# espbot.net
KiCad netlist of a schematic drawn in EAGLE
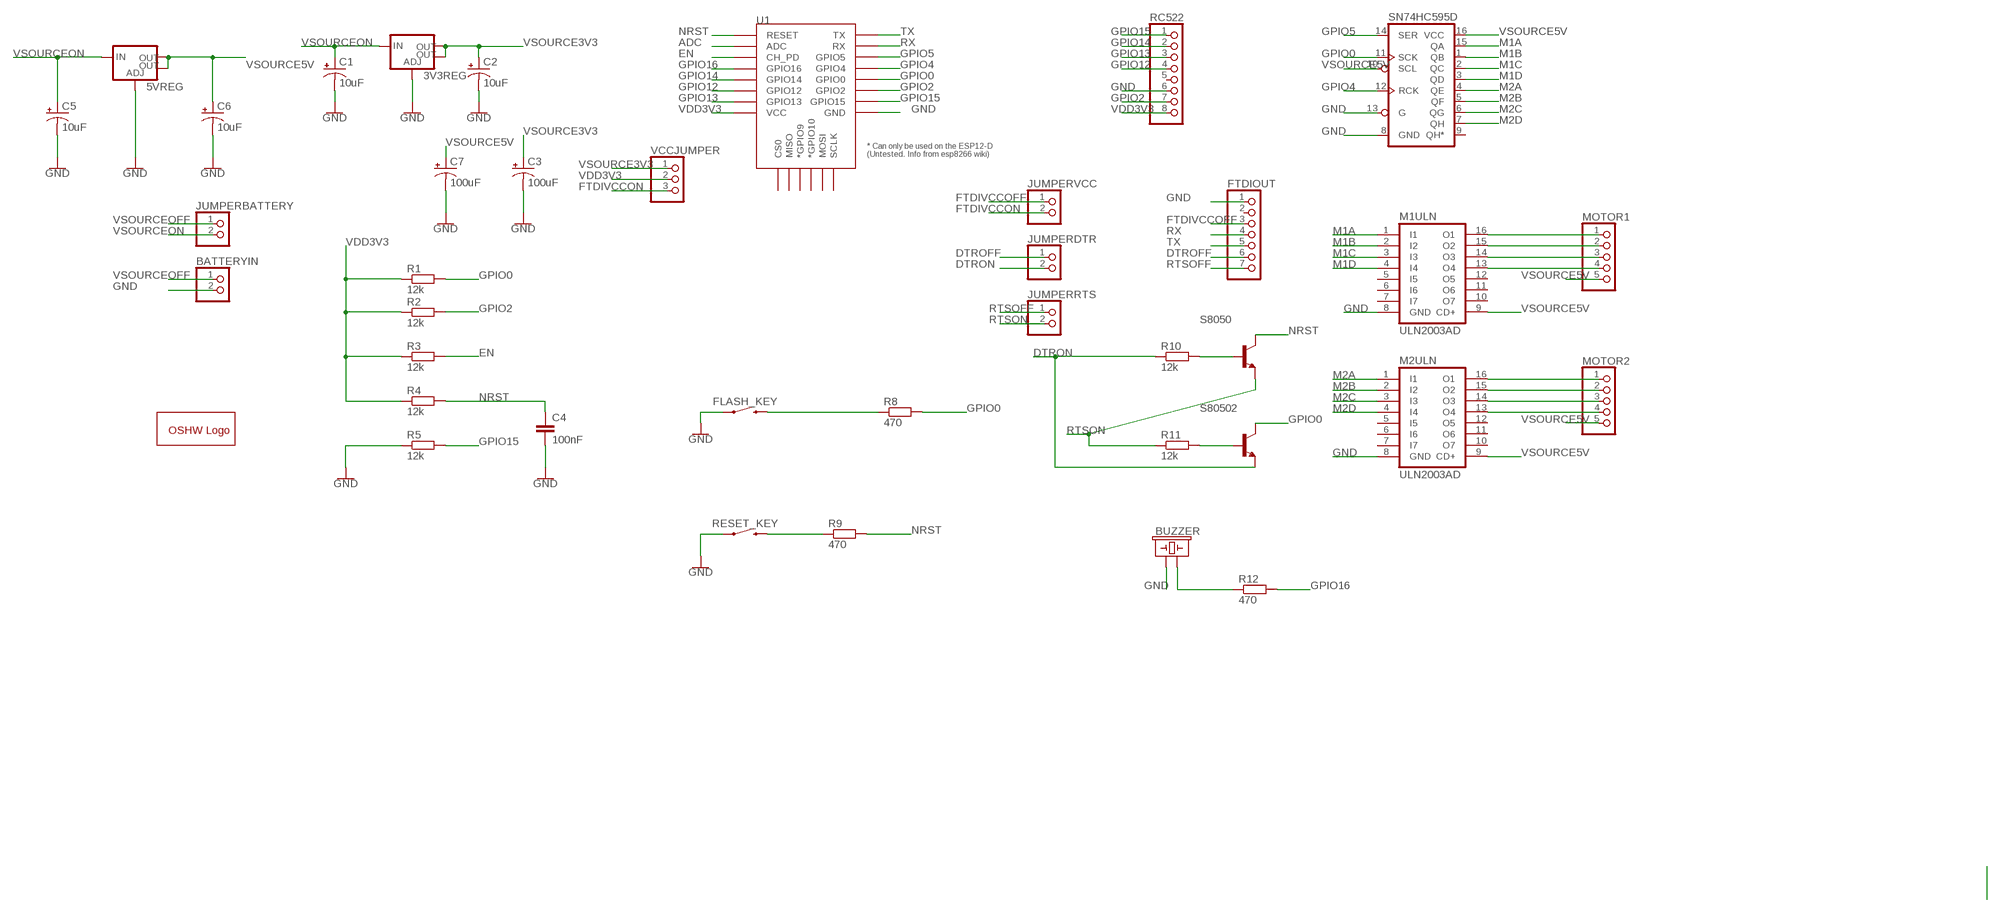
[diagram p0: schematic, sheet 1]

(export (version "E")
  (design (tool "Eeschema 10.0.6"))
  (components
    (comp (ref "3V3REG")
      (value "V_REG_LM1117SOT223")
      (footprint "eagle-import:SOT223")
      (libsource (lib "eagle-import") (part "V_REG_LM1117SOT223"))
    )
    (comp (ref "5VREG")
      (value "V_REG_LM1117SOT223")
      (footprint "eagle-import:SOT223")
      (libsource (lib "eagle-import") (part "V_REG_LM1117SOT223"))
    )
    (comp (ref "BATTERYIN")
      (value "PINHD-1X2")
      (footprint "eagle-import:1X02")
      (libsource (lib "eagle-import") (part "PINHD-1X2"))
    )
    (comp (ref "BUZZER")
      (value "BUZZER-PTH")
      (footprint "eagle-import:BUZZER-12MM")
      (libsource (lib "eagle-import") (part "BUZZER-PTH"))
    )
    (comp (ref "C1")
      (value "10uF")
      (footprint "eagle-import:EIA3528")
      (libsource (lib "eagle-import") (part "10UF-POLAR-EIA3528-20V-10%(TANT)"))
    )
    (comp (ref "C2")
      (value "10uF")
      (footprint "eagle-import:EIA3528")
      (libsource (lib "eagle-import") (part "10UF-POLAR-EIA3528-20V-10%(TANT)"))
    )
    (comp (ref "C3")
      (value "100uF")
      (footprint "eagle-import:EIA7343")
      (libsource (lib "eagle-import") (part "100UF-POLAR-EIA7343-10V-10%(TANT)"))
    )
    (comp (ref "C4")
      (value "100nF")
      (footprint "eagle-import:C0805")
      (libsource (lib "eagle-import") (part "C-EUC0805"))
    )
    (comp (ref "C5")
      (value "10uF")
      (footprint "eagle-import:EIA3528")
      (libsource (lib "eagle-import") (part "10UF-POLAR-EIA3528-20V-10%(TANT)"))
    )
    (comp (ref "C6")
      (value "10uF")
      (footprint "eagle-import:EIA3528")
      (libsource (lib "eagle-import") (part "10UF-POLAR-EIA3528-20V-10%(TANT)"))
    )
    (comp (ref "C7")
      (value "100uF")
      (footprint "eagle-import:EIA7343")
      (libsource (lib "eagle-import") (part "100UF-POLAR-EIA7343-10V-10%(TANT)"))
    )
    (comp (ref "FLASH_KEY")
      (value "MOMENTARY-SWITCH-SPST-PTH-6.0MM")
      (footprint "eagle-import:TACTILE_SWITCH_PTH_6.0MM")
      (libsource (lib "eagle-import") (part "MOMENTARY-SWITCH-SPST-PTH-6.0MM"))
    )
    (comp (ref "FTDIOUT")
      (value "PINHD-1X7")
      (footprint "eagle-import:1X07")
      (libsource (lib "eagle-import") (part "PINHD-1X7"))
    )
    (comp (ref "GOLD_ORB_SM1")
      (value "OSHWLOGOLOGO5MM")
      (footprint "eagle-import:OSHW_5MM")
      (libsource (lib "eagle-import") (part "OSHWLOGOLOGO5MM"))
    )
    (comp (ref "JUMPERBATTERY")
      (value "PINHD-1X2")
      (footprint "eagle-import:1X02")
      (libsource (lib "eagle-import") (part "PINHD-1X2"))
    )
    (comp (ref "JUMPERDTR")
      (value "PINHD-1X2")
      (footprint "eagle-import:1X02")
      (libsource (lib "eagle-import") (part "PINHD-1X2"))
    )
    (comp (ref "JUMPERRTS")
      (value "PINHD-1X2")
      (footprint "eagle-import:1X02")
      (libsource (lib "eagle-import") (part "PINHD-1X2"))
    )
    (comp (ref "JUMPERVCC")
      (value "PINHD-1X2")
      (footprint "eagle-import:1X02")
      (libsource (lib "eagle-import") (part "PINHD-1X2"))
    )
    (comp (ref "M1ULN")
      (value "ULN2003AD")
      (footprint "eagle-import:SO16")
      (libsource (lib "eagle-import") (part "ULN2003AD"))
    )
    (comp (ref "M2ULN")
      (value "ULN2003AD")
      (footprint "eagle-import:SO16")
      (libsource (lib "eagle-import") (part "ULN2003AD"))
    )
    (comp (ref "MOTOR1")
      (value "PINHD-1X5")
      (footprint "eagle-import:1X05")
      (libsource (lib "eagle-import") (part "PINHD-1X5"))
    )
    (comp (ref "MOTOR2")
      (value "PINHD-1X5")
      (footprint "eagle-import:1X05")
      (libsource (lib "eagle-import") (part "PINHD-1X5"))
    )
    (comp (ref "R1")
      (value "12k")
      (footprint "eagle-import:R0805")
      (libsource (lib "eagle-import") (part "R-EU_R0805"))
    )
    (comp (ref "R2")
      (value "12k")
      (footprint "eagle-import:R0805")
      (libsource (lib "eagle-import") (part "R-EU_R0805"))
    )
    (comp (ref "R3")
      (value "12k")
      (footprint "eagle-import:R0805")
      (libsource (lib "eagle-import") (part "R-EU_R0805"))
    )
    (comp (ref "R4")
      (value "12k")
      (footprint "eagle-import:R0805")
      (libsource (lib "eagle-import") (part "R-EU_R0805"))
    )
    (comp (ref "R5")
      (value "12k")
      (footprint "eagle-import:R0805")
      (libsource (lib "eagle-import") (part "R-EU_R0805"))
    )
    (comp (ref "R8")
      (value "470")
      (footprint "eagle-import:R0805")
      (libsource (lib "eagle-import") (part "R-EU_R0805"))
    )
    (comp (ref "R9")
      (value "470")
      (footprint "eagle-import:R0805")
      (libsource (lib "eagle-import") (part "R-EU_R0805"))
    )
    (comp (ref "R10")
      (value "12k")
      (footprint "eagle-import:R0805")
      (libsource (lib "eagle-import") (part "R-EU_R0805"))
    )
    (comp (ref "R11")
      (value "12k")
      (footprint "eagle-import:R0805")
      (libsource (lib "eagle-import") (part "R-EU_R0805"))
    )
    (comp (ref "R12")
      (value "470")
      (footprint "eagle-import:R0805")
      (libsource (lib "eagle-import") (part "R-EU_R0805"))
    )
    (comp (ref "RC522")
      (value "PINHD-1X8")
      (footprint "eagle-import:1X08")
      (libsource (lib "eagle-import") (part "PINHD-1X8"))
    )
    (comp (ref "RESET_KEY")
      (value "MOMENTARY-SWITCH-SPST-PTH-6.0MM")
      (footprint "eagle-import:TACTILE_SWITCH_PTH_6.0MM")
      (libsource (lib "eagle-import") (part "MOMENTARY-SWITCH-SPST-PTH-6.0MM"))
    )
    (comp (ref "S8050")
      (value "92-NPN-TO92-EBC")
      (footprint "eagle-import:TO92-EBC")
      (libsource (lib "eagle-import") (part "-NPN-TO92-EBC92"))
    )
    (comp (ref "S80502")
      (value "92-NPN-TO92-EBC")
      (footprint "eagle-import:TO92-EBC")
      (libsource (lib "eagle-import") (part "-NPN-TO92-EBC92"))
    )
    (comp (ref "SN74HC595D")
      (value "74HC595D")
      (footprint "eagle-import:SO16")
      (libsource (lib "eagle-import") (part "74595DHC"))
    )
    (comp (ref "U1")
      (value "ESP12ESMD")
      (footprint "eagle-import:ESP12E-SMD")
      (libsource (lib "eagle-import") (part "ESP12ESMD"))
    )
    (comp (ref "VCCJUMPER")
      (value "PINHD-1X3")
      (footprint "eagle-import:1X03")
      (libsource (lib "eagle-import") (part "PINHD-1X3"))
    )
  )
  (nets
    (net (code "1") (name "/ADC") (class "Default")
      (node (ref "U1") (pin "ADC") (pinfunction "ADC_ADC") (pintype "bidirectional"))
    )
    (net (code "2") (name "/DTROFF") (class "Default")
      (node (ref "FTDIOUT") (pin "6") (pinfunction "6_6") (pintype "passive"))
      (node (ref "JUMPERDTR") (pin "1") (pinfunction "1_1") (pintype "passive"))
    )
    (net (code "3") (name "/DTRON") (class "Default")
      (node (ref "JUMPERDTR") (pin "2") (pinfunction "2_2") (pintype "passive"))
      (node (ref "R10") (pin "1") (pinfunction "1_1") (pintype "passive"))
      (node (ref "S80502") (pin "E") (pinfunction "E_E") (pintype "passive"))
    )
    (net (code "4") (name "/EN") (class "Default")
      (node (ref "R3") (pin "2") (pinfunction "2_2") (pintype "passive"))
      (node (ref "U1") (pin "CH_PD") (pinfunction "CH_PD_CH_PD") (pintype "bidirectional"))
    )
    (net (code "5") (name "/FTDIVCCOFF") (class "Default")
      (node (ref "FTDIOUT") (pin "3") (pinfunction "3_3") (pintype "passive"))
      (node (ref "JUMPERVCC") (pin "1") (pinfunction "1_1") (pintype "passive"))
    )
    (net (code "6") (name "/FTDIVCCON") (class "Default")
      (node (ref "JUMPERVCC") (pin "2") (pinfunction "2_2") (pintype "passive"))
      (node (ref "VCCJUMPER") (pin "3") (pinfunction "3_3") (pintype "passive"))
    )
    (net (code "7") (name "/GPIO0") (class "Default")
      (node (ref "R1") (pin "2") (pinfunction "2_2") (pintype "passive"))
      (node (ref "R8") (pin "2") (pinfunction "2_2") (pintype "passive"))
      (node (ref "S80502") (pin "C") (pinfunction "C_C") (pintype "passive"))
      (node (ref "SN74HC595D") (pin "11") (pinfunction "SCK_11") (pintype "input"))
      (node (ref "U1") (pin "GPIO0") (pinfunction "GPIO0_GPIO0") (pintype "bidirectional"))
    )
    (net (code "8") (name "/GPIO2") (class "Default")
      (node (ref "R2") (pin "2") (pinfunction "2_2") (pintype "passive"))
      (node (ref "RC522") (pin "7") (pinfunction "7_7") (pintype "passive"))
      (node (ref "U1") (pin "GPIO2") (pinfunction "GPIO2_GPIO2") (pintype "bidirectional"))
    )
    (net (code "9") (name "/GPIO4") (class "Default")
      (node (ref "SN74HC595D") (pin "12") (pinfunction "RCK_12") (pintype "input"))
      (node (ref "U1") (pin "GPIO4") (pinfunction "GPIO4_GPIO4") (pintype "bidirectional"))
    )
    (net (code "10") (name "/GPIO5") (class "Default")
      (node (ref "SN74HC595D") (pin "14") (pinfunction "SER_14") (pintype "input"))
      (node (ref "U1") (pin "GPIO5") (pinfunction "GPIO5_GPIO5") (pintype "bidirectional"))
    )
    (net (code "11") (name "/GPIO12") (class "Default")
      (node (ref "RC522") (pin "4") (pinfunction "4_4") (pintype "passive"))
      (node (ref "U1") (pin "GPIO12") (pinfunction "GPIO12_GPIO12") (pintype "bidirectional"))
    )
    (net (code "12") (name "/GPIO13") (class "Default")
      (node (ref "RC522") (pin "3") (pinfunction "3_3") (pintype "passive"))
      (node (ref "U1") (pin "GPIO13") (pinfunction "GPIO13_GPIO13") (pintype "bidirectional"))
    )
    (net (code "13") (name "/GPIO14") (class "Default")
      (node (ref "RC522") (pin "2") (pinfunction "2_2") (pintype "passive"))
      (node (ref "U1") (pin "GPIO14") (pinfunction "GPIO14_GPIO14") (pintype "bidirectional"))
    )
    (net (code "14") (name "/GPIO15") (class "Default")
      (node (ref "R5") (pin "2") (pinfunction "2_2") (pintype "passive"))
      (node (ref "RC522") (pin "1") (pinfunction "1_1") (pintype "passive"))
      (node (ref "U1") (pin "GPIO15") (pinfunction "GPIO15_GPIO15") (pintype "bidirectional"))
    )
    (net (code "15") (name "/GPIO16") (class "Default")
      (node (ref "R12") (pin "2") (pinfunction "2_2") (pintype "passive"))
      (node (ref "U1") (pin "GPIO16") (pinfunction "GPIO16_GPIO16") (pintype "bidirectional"))
    )
    (net (code "16") (name "/M1A") (class "Default")
      (node (ref "M1ULN") (pin "1") (pinfunction "I1_1") (pintype "input"))
      (node (ref "SN74HC595D") (pin "15") (pinfunction "QA_15") (pintype "tri_state"))
    )
    (net (code "17") (name "/M1B") (class "Default")
      (node (ref "M1ULN") (pin "2") (pinfunction "I2_2") (pintype "input"))
      (node (ref "SN74HC595D") (pin "1") (pinfunction "QB_1") (pintype "tri_state"))
    )
    (net (code "18") (name "/M1C") (class "Default")
      (node (ref "M1ULN") (pin "3") (pinfunction "I3_3") (pintype "input"))
      (node (ref "SN74HC595D") (pin "2") (pinfunction "QC_2") (pintype "tri_state"))
    )
    (net (code "19") (name "/M1D") (class "Default")
      (node (ref "M1ULN") (pin "4") (pinfunction "I4_4") (pintype "input"))
      (node (ref "SN74HC595D") (pin "3") (pinfunction "QD_3") (pintype "tri_state"))
    )
    (net (code "20") (name "/M2A") (class "Default")
      (node (ref "M2ULN") (pin "1") (pinfunction "I1_1") (pintype "input"))
      (node (ref "SN74HC595D") (pin "4") (pinfunction "QE_4") (pintype "tri_state"))
    )
    (net (code "21") (name "/M2B") (class "Default")
      (node (ref "M2ULN") (pin "2") (pinfunction "I2_2") (pintype "input"))
      (node (ref "SN74HC595D") (pin "5") (pinfunction "QF_5") (pintype "tri_state"))
    )
    (net (code "22") (name "/M2C") (class "Default")
      (node (ref "M2ULN") (pin "3") (pinfunction "I3_3") (pintype "input"))
      (node (ref "SN74HC595D") (pin "6") (pinfunction "QG_6") (pintype "tri_state"))
    )
    (net (code "23") (name "/M2D") (class "Default")
      (node (ref "M2ULN") (pin "4") (pinfunction "I4_4") (pintype "input"))
      (node (ref "SN74HC595D") (pin "7") (pinfunction "QH_7") (pintype "tri_state"))
    )
    (net (code "24") (name "/NRST") (class "Default")
      (node (ref "C4") (pin "1") (pinfunction "1_1") (pintype "passive"))
      (node (ref "R4") (pin "2") (pinfunction "2_2") (pintype "passive"))
      (node (ref "R9") (pin "2") (pinfunction "2_2") (pintype "passive"))
      (node (ref "S8050") (pin "C") (pinfunction "C_C") (pintype "passive"))
      (node (ref "U1") (pin "RESET") (pinfunction "RESET_RESET") (pintype "bidirectional"))
    )
    (net (code "25") (name "/RTSOFF") (class "Default")
      (node (ref "FTDIOUT") (pin "7") (pinfunction "7_7") (pintype "passive"))
      (node (ref "JUMPERRTS") (pin "1") (pinfunction "1_1") (pintype "passive"))
    )
    (net (code "26") (name "/RTSON") (class "Default")
      (node (ref "JUMPERRTS") (pin "2") (pinfunction "2_2") (pintype "passive"))
      (node (ref "R11") (pin "1") (pinfunction "1_1") (pintype "passive"))
      (node (ref "S8050") (pin "E") (pinfunction "E_E") (pintype "passive"))
    )
    (net (code "27") (name "/RX") (class "Default")
      (node (ref "FTDIOUT") (pin "4") (pinfunction "4_4") (pintype "passive"))
      (node (ref "U1") (pin "RXD0") (pinfunction "RX_RXD0") (pintype "bidirectional"))
    )
    (net (code "28") (name "/TX") (class "Default")
      (node (ref "FTDIOUT") (pin "5") (pinfunction "5_5") (pintype "passive"))
      (node (ref "U1") (pin "TXD0") (pinfunction "TX_TXD0") (pintype "bidirectional"))
    )
    (net (code "29") (name "/VDD3V3") (class "Default")
      (node (ref "R1") (pin "1") (pinfunction "1_1") (pintype "passive"))
      (node (ref "R2") (pin "1") (pinfunction "1_1") (pintype "passive"))
      (node (ref "R3") (pin "1") (pinfunction "1_1") (pintype "passive"))
      (node (ref "R4") (pin "1") (pinfunction "1_1") (pintype "passive"))
      (node (ref "RC522") (pin "8") (pinfunction "8_8") (pintype "passive"))
      (node (ref "U1") (pin "VCC") (pinfunction "VCC_VCC") (pintype "bidirectional"))
      (node (ref "VCCJUMPER") (pin "2") (pinfunction "2_2") (pintype "passive"))
    )
    (net (code "30") (name "/VSOURCE3V3") (class "Default")
      (node (ref "3V3REG") (pin "2") (pinfunction "OUT_2") (pintype "output"))
      (node (ref "3V3REG") (pin "4") (pinfunction "OUT_4") (pintype "output"))
      (node (ref "C2") (pin "A") (pinfunction "+_A") (pintype "passive"))
      (node (ref "C3") (pin "A") (pinfunction "+_A") (pintype "passive"))
      (node (ref "VCCJUMPER") (pin "1") (pinfunction "1_1") (pintype "passive"))
    )
    (net (code "31") (name "/VSOURCE5V") (class "Default")
      (node (ref "5VREG") (pin "2") (pinfunction "OUT_2") (pintype "output"))
      (node (ref "5VREG") (pin "4") (pinfunction "OUT_4") (pintype "output"))
      (node (ref "C6") (pin "A") (pinfunction "+_A") (pintype "passive"))
      (node (ref "C7") (pin "A") (pinfunction "+_A") (pintype "passive"))
      (node (ref "M1ULN") (pin "9") (pinfunction "CD+_9") (pintype "passive"))
      (node (ref "M2ULN") (pin "9") (pinfunction "CD+_9") (pintype "passive"))
      (node (ref "MOTOR1") (pin "5") (pinfunction "5_5") (pintype "passive"))
      (node (ref "MOTOR2") (pin "5") (pinfunction "5_5") (pintype "passive"))
      (node (ref "SN74HC595D") (pin "10") (pinfunction "SCL_10") (pintype "input"))
      (node (ref "SN74HC595D") (pin "16") (pinfunction "VCC_16") (pintype "power_in"))
    )
    (net (code "32") (name "/VSOURCEOFF") (class "Default")
      (node (ref "BATTERYIN") (pin "1") (pinfunction "1_1") (pintype "passive"))
      (node (ref "JUMPERBATTERY") (pin "1") (pinfunction "1_1") (pintype "passive"))
    )
    (net (code "33") (name "/VSOURCEON") (class "Default")
      (node (ref "3V3REG") (pin "3") (pinfunction "IN_3") (pintype "input"))
      (node (ref "5VREG") (pin "3") (pinfunction "IN_3") (pintype "input"))
      (node (ref "C1") (pin "A") (pinfunction "+_A") (pintype "passive"))
      (node (ref "C5") (pin "A") (pinfunction "+_A") (pintype "passive"))
      (node (ref "JUMPERBATTERY") (pin "2") (pinfunction "2_2") (pintype "passive"))
    )
    (net (code "34") (name "GND") (class "Default")
      (node (ref "3V3REG") (pin "1") (pinfunction "ADJ_1") (pintype "input"))
      (node (ref "5VREG") (pin "1") (pinfunction "ADJ_1") (pintype "input"))
      (node (ref "BATTERYIN") (pin "2") (pinfunction "2_2") (pintype "passive"))
      (node (ref "BUZZER") (pin "+") (pinfunction "1_+") (pintype "passive"))
      (node (ref "C1") (pin "C") (pinfunction "-_C") (pintype "passive"))
      (node (ref "C2") (pin "C") (pinfunction "-_C") (pintype "passive"))
      (node (ref "C3") (pin "C") (pinfunction "-_C") (pintype "passive"))
      (node (ref "C4") (pin "2") (pinfunction "2_2") (pintype "passive"))
      (node (ref "C5") (pin "C") (pinfunction "-_C") (pintype "passive"))
      (node (ref "C6") (pin "C") (pinfunction "-_C") (pintype "passive"))
      (node (ref "C7") (pin "C") (pinfunction "-_C") (pintype "passive"))
      (node (ref "FLASH_KEY") (pin "1") (pinfunction "1_1") (pintype "passive"))
      (node (ref "FTDIOUT") (pin "1") (pinfunction "1_1") (pintype "passive"))
      (node (ref "M1ULN") (pin "8") (pinfunction "GND_8") (pintype "power_in"))
      (node (ref "M2ULN") (pin "8") (pinfunction "GND_8") (pintype "power_in"))
      (node (ref "R5") (pin "1") (pinfunction "1_1") (pintype "passive"))
      (node (ref "RC522") (pin "6") (pinfunction "6_6") (pintype "passive"))
      (node (ref "RESET_KEY") (pin "1") (pinfunction "1_1") (pintype "passive"))
      (node (ref "SN74HC595D") (pin "13") (pinfunction "G_13") (pintype "input"))
      (node (ref "SN74HC595D") (pin "8") (pinfunction "GND_8") (pintype "power_in"))
      (node (ref "U1") (pin "GND") (pinfunction "GND_GND") (pintype "bidirectional"))
    )
    (net (code "35") (name "Net-(BUZZER-2)") (class "Default")
      (node (ref "BUZZER") (pin "-") (pinfunction "2_-") (pintype "passive"))
      (node (ref "R12") (pin "1") (pinfunction "1_1") (pintype "passive"))
    )
    (net (code "36") (name "Net-(FLASH_KEY-2)") (class "Default")
      (node (ref "FLASH_KEY") (pin "3") (pinfunction "2_3") (pintype "passive"))
      (node (ref "R8") (pin "1") (pinfunction "1_1") (pintype "passive"))
    )
    (net (code "37") (name "Net-(M1ULN-O1)") (class "Default")
      (node (ref "M1ULN") (pin "16") (pinfunction "O1_16") (pintype "open_collector"))
      (node (ref "MOTOR1") (pin "1") (pinfunction "1_1") (pintype "passive"))
    )
    (net (code "38") (name "Net-(M1ULN-O2)") (class "Default")
      (node (ref "M1ULN") (pin "15") (pinfunction "O2_15") (pintype "open_collector"))
      (node (ref "MOTOR1") (pin "2") (pinfunction "2_2") (pintype "passive"))
    )
    (net (code "39") (name "Net-(M1ULN-O3)") (class "Default")
      (node (ref "M1ULN") (pin "14") (pinfunction "O3_14") (pintype "open_collector"))
      (node (ref "MOTOR1") (pin "3") (pinfunction "3_3") (pintype "passive"))
    )
    (net (code "40") (name "Net-(M1ULN-O4)") (class "Default")
      (node (ref "M1ULN") (pin "13") (pinfunction "O4_13") (pintype "open_collector"))
      (node (ref "MOTOR1") (pin "4") (pinfunction "4_4") (pintype "passive"))
    )
    (net (code "41") (name "Net-(M2ULN-O1)") (class "Default")
      (node (ref "M2ULN") (pin "16") (pinfunction "O1_16") (pintype "open_collector"))
      (node (ref "MOTOR2") (pin "1") (pinfunction "1_1") (pintype "passive"))
    )
    (net (code "42") (name "Net-(M2ULN-O2)") (class "Default")
      (node (ref "M2ULN") (pin "15") (pinfunction "O2_15") (pintype "open_collector"))
      (node (ref "MOTOR2") (pin "2") (pinfunction "2_2") (pintype "passive"))
    )
    (net (code "43") (name "Net-(M2ULN-O3)") (class "Default")
      (node (ref "M2ULN") (pin "14") (pinfunction "O3_14") (pintype "open_collector"))
      (node (ref "MOTOR2") (pin "3") (pinfunction "3_3") (pintype "passive"))
    )
    (net (code "44") (name "Net-(M2ULN-O4)") (class "Default")
      (node (ref "M2ULN") (pin "13") (pinfunction "O4_13") (pintype "open_collector"))
      (node (ref "MOTOR2") (pin "4") (pinfunction "4_4") (pintype "passive"))
    )
    (net (code "45") (name "Net-(R10-Pad2)") (class "Default")
      (node (ref "R10") (pin "2") (pinfunction "2_2") (pintype "passive"))
      (node (ref "S8050") (pin "B") (pinfunction "B_B") (pintype "passive"))
    )
    (net (code "46") (name "Net-(R11-Pad2)") (class "Default")
      (node (ref "R11") (pin "2") (pinfunction "2_2") (pintype "passive"))
      (node (ref "S80502") (pin "B") (pinfunction "B_B") (pintype "passive"))
    )
    (net (code "47") (name "Net-(RESET_KEY-2)") (class "Default")
      (node (ref "R9") (pin "1") (pinfunction "1_1") (pintype "passive"))
      (node (ref "RESET_KEY") (pin "3") (pinfunction "2_3") (pintype "passive"))
    )
    (net (code "48") (name "unconnected-(FTDIOUT-Pad2)") (class "Default")
      (node (ref "FTDIOUT") (pin "2") (pinfunction "2_2") (pintype "passive"))
    )
    (net (code "49") (name "unconnected-(M1ULN-I5-Pad5)") (class "Default")
      (node (ref "M1ULN") (pin "5") (pinfunction "I5_5") (pintype "input"))
    )
    (net (code "50") (name "unconnected-(M1ULN-I6-Pad6)") (class "Default")
      (node (ref "M1ULN") (pin "6") (pinfunction "I6_6") (pintype "input"))
    )
    (net (code "51") (name "unconnected-(M1ULN-I7-Pad7)") (class "Default")
      (node (ref "M1ULN") (pin "7") (pinfunction "I7_7") (pintype "input"))
    )
    (net (code "52") (name "unconnected-(M1ULN-O5-Pad12)") (class "Default")
      (node (ref "M1ULN") (pin "12") (pinfunction "O5_12") (pintype "open_collector"))
    )
    (net (code "53") (name "unconnected-(M1ULN-O6-Pad11)") (class "Default")
      (node (ref "M1ULN") (pin "11") (pinfunction "O6_11") (pintype "open_collector"))
    )
    (net (code "54") (name "unconnected-(M1ULN-O7-Pad10)") (class "Default")
      (node (ref "M1ULN") (pin "10") (pinfunction "O7_10") (pintype "open_collector"))
    )
    (net (code "55") (name "unconnected-(M2ULN-I5-Pad5)") (class "Default")
      (node (ref "M2ULN") (pin "5") (pinfunction "I5_5") (pintype "input"))
    )
    (net (code "56") (name "unconnected-(M2ULN-I6-Pad6)") (class "Default")
      (node (ref "M2ULN") (pin "6") (pinfunction "I6_6") (pintype "input"))
    )
    (net (code "57") (name "unconnected-(M2ULN-I7-Pad7)") (class "Default")
      (node (ref "M2ULN") (pin "7") (pinfunction "I7_7") (pintype "input"))
    )
    (net (code "58") (name "unconnected-(M2ULN-O5-Pad12)") (class "Default")
      (node (ref "M2ULN") (pin "12") (pinfunction "O5_12") (pintype "open_collector"))
    )
    (net (code "59") (name "unconnected-(M2ULN-O6-Pad11)") (class "Default")
      (node (ref "M2ULN") (pin "11") (pinfunction "O6_11") (pintype "open_collector"))
    )
    (net (code "60") (name "unconnected-(M2ULN-O7-Pad10)") (class "Default")
      (node (ref "M2ULN") (pin "10") (pinfunction "O7_10") (pintype "open_collector"))
    )
    (net (code "61") (name "unconnected-(RC522-Pad5)") (class "Default")
      (node (ref "RC522") (pin "5") (pinfunction "5_5") (pintype "passive"))
    )
    (net (code "62") (name "unconnected-(SN74HC595D-QH*-Pad9)") (class "Default")
      (node (ref "SN74HC595D") (pin "9") (pinfunction "QH*_9") (pintype "tri_state"))
    )
    (net (code "63") (name "unconnected-(U1-*GPIO9-PadGPIO9)") (class "Default")
      (node (ref "U1") (pin "GPIO9") (pinfunction "*GPIO9_GPIO9") (pintype "bidirectional"))
    )
    (net (code "64") (name "unconnected-(U1-*GPIO10-PadGPIO10)") (class "Default")
      (node (ref "U1") (pin "GPIO10") (pinfunction "*GPIO10_GPIO10") (pintype "bidirectional"))
    )
    (net (code "65") (name "unconnected-(U1-PadCS0)") (class "Default")
      (node (ref "U1") (pin "CS0") (pinfunction "CS0_CS0") (pintype "bidirectional"))
    )
    (net (code "66") (name "unconnected-(U1-PadMISO)") (class "Default")
      (node (ref "U1") (pin "MISO") (pinfunction "MISO_MISO") (pintype "bidirectional"))
    )
    (net (code "67") (name "unconnected-(U1-PadMOSI)") (class "Default")
      (node (ref "U1") (pin "MOSI") (pinfunction "MOSI_MOSI") (pintype "bidirectional"))
    )
    (net (code "68") (name "unconnected-(U1-PadSCLK)") (class "Default")
      (node (ref "U1") (pin "SCLK") (pinfunction "SCLK_SCLK") (pintype "bidirectional"))
    )
  )
)
